# Power.net
KiCad netlist of a schematic drawn in Altium Designer
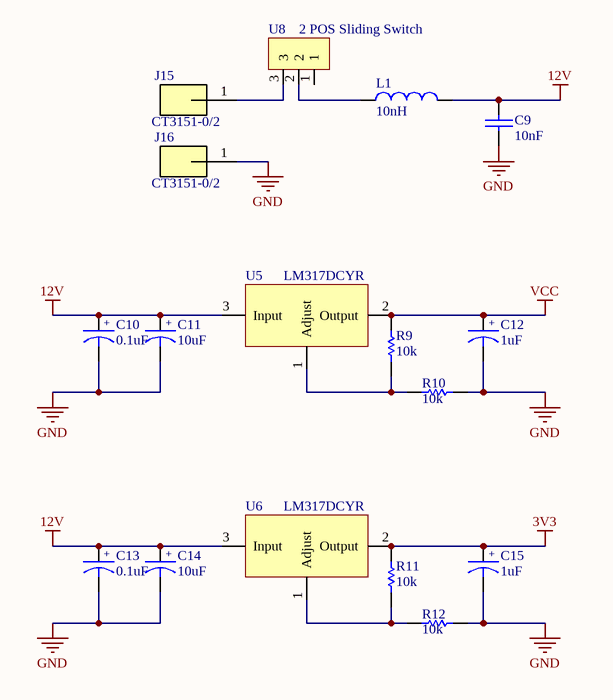
[diagram p0: Power.SchDoc]

(export (version "E")
  (design (tool "Eeschema 10.0.6"))
  (components
    (comp (ref "C9")
      (value "10nF")
      (footprint "0603C")
      (description "Capacitor")
      (libsource (lib "GENERIC_LIB") (part "C"))
    )
    (comp (ref "C10")
      (value "0.1uF")
      (footprint "0603C")
      (description "Cap Poly")
      (libsource (lib "GENERIC_LIB") (part "CPoly"))
    )
    (comp (ref "C11")
      (value "10uF")
      (footprint "0603C")
      (description "Cap Poly")
      (libsource (lib "GENERIC_LIB") (part "CPoly"))
    )
    (comp (ref "C12")
      (value "1uF")
      (footprint "0603C")
      (description "Cap Poly")
      (libsource (lib "GENERIC_LIB") (part "CPoly"))
    )
    (comp (ref "C13")
      (value "0.1uF")
      (footprint "0603C")
      (description "Cap Poly")
      (libsource (lib "GENERIC_LIB") (part "CPoly"))
    )
    (comp (ref "C14")
      (value "10uF")
      (footprint "0603C")
      (description "Cap Poly")
      (libsource (lib "GENERIC_LIB") (part "CPoly"))
    )
    (comp (ref "C15")
      (value "1uF")
      (footprint "0603C")
      (description "Cap Poly")
      (libsource (lib "GENERIC_LIB") (part "CPoly"))
    )
    (comp (ref "J15")
      (value "CT3151-0/2")
      (footprint "CT3151-0/2")
      (description "CONN BANANA JACK SOLDER BLACK")
      (fields
        (field (name "MF") "Cal Test Electronics")
        (field (name "DIGI-KEY_PART_NUMBER") "BKCT3151-0-ND")
      )
      (libsource (lib "CON_LIB") (part "CT3151-0/2"))
    )
    (comp (ref "J16")
      (value "CT3151-0/2")
      (footprint "CT3151-0/2")
      (description "CONN BANANA JACK SOLDER BLACK")
      (fields
        (field (name "MF") "Cal Test Electronics")
        (field (name "DIGI-KEY_PART_NUMBER") "BKCT3151-0-ND")
      )
      (libsource (lib "CON_LIB") (part "CT3151-0/2"))
    )
    (comp (ref "L1")
      (value "10nH")
      (footprint "0603C")
      (description "Inductor")
      (libsource (lib "GENERIC_LIB") (part "L"))
    )
    (comp (ref "R9")
      (value "10k")
      (footprint "0603C")
      (description "Resistor")
      (fields (field (name "TOLERANCE") "5%"))
      (libsource (lib "GENERIC_LIB") (part "R"))
    )
    (comp (ref "R10")
      (value "10k")
      (footprint "0603C")
      (description "Resistor")
      (fields (field (name "TOLERANCE") "5%"))
      (libsource (lib "GENERIC_LIB") (part "R"))
    )
    (comp (ref "R11")
      (value "10k")
      (footprint "0603C")
      (description "Resistor")
      (fields (field (name "TOLERANCE") "5%"))
      (libsource (lib "GENERIC_LIB") (part "R"))
    )
    (comp (ref "R12")
      (value "10k")
      (footprint "0603C")
      (description "Resistor")
      (fields (field (name "TOLERANCE") "5%"))
      (libsource (lib "GENERIC_LIB") (part "R"))
    )
    (comp (ref "U5") (value "LM317DCYR") (footprint "LM317") (libsource (lib "IC_POWER_LIB") (part "LM317")))
    (comp (ref "U6") (value "LM317DCYR") (footprint "LM317") (libsource (lib "IC_POWER_LIB") (part "LM317")))
    (comp (ref "U8")
      (value "2 POS Sliding Switch")
      (footprint "2 POS Sliding switch")
      (libsource (lib "CON_LIB") (part "2 POS Sliding Switch"))
    )
  )
  (nets
    (net (code "1") (name "3V3") (class "Default")
      (node (ref "C15") (pin "1") (pinfunction "1_1") (pintype "passive"))
      (node (ref "R11") (pin "2") (pinfunction "2_2") (pintype "passive"))
      (node (ref "U6") (pin "2") (pinfunction "Output_2") (pintype "passive"))
    )
    (net (code "2") (name "12V") (class "Default")
      (node (ref "C10") (pin "1") (pinfunction "1_1") (pintype "passive"))
      (node (ref "C11") (pin "1") (pinfunction "1_1") (pintype "passive"))
      (node (ref "C13") (pin "1") (pinfunction "1_1") (pintype "passive"))
      (node (ref "C14") (pin "1") (pinfunction "1_1") (pintype "passive"))
      (node (ref "C9") (pin "1") (pinfunction "1_1") (pintype "passive"))
      (node (ref "L1") (pin "2") (pinfunction "2_2") (pintype "passive"))
      (node (ref "U5") (pin "3") (pinfunction "Input_3") (pintype "passive"))
      (node (ref "U6") (pin "3") (pinfunction "Input_3") (pintype "passive"))
    )
    (net (code "3") (name "GND") (class "Default")
      (node (ref "C10") (pin "2") (pinfunction "2_2") (pintype "passive"))
      (node (ref "C11") (pin "2") (pinfunction "2_2") (pintype "passive"))
      (node (ref "C12") (pin "2") (pinfunction "2_2") (pintype "passive"))
      (node (ref "C13") (pin "2") (pinfunction "2_2") (pintype "passive"))
      (node (ref "C14") (pin "2") (pinfunction "2_2") (pintype "passive"))
      (node (ref "C15") (pin "2") (pinfunction "2_2") (pintype "passive"))
      (node (ref "C9") (pin "2") (pinfunction "2_2") (pintype "passive"))
      (node (ref "J16") (pin "1") (pintype "power_in"))
      (node (ref "R10") (pin "2") (pinfunction "2_2") (pintype "passive"))
      (node (ref "R12") (pin "2") (pinfunction "2_2") (pintype "passive"))
    )
    (net (code "4") (name "Net-(J15-Pad1)") (class "Default")
      (node (ref "J15") (pin "1") (pintype "power_in"))
      (node (ref "U8") (pin "3") (pinfunction "3_3") (pintype "passive"))
    )
    (net (code "5") (name "Net-(L1-Pad1)") (class "Default")
      (node (ref "L1") (pin "1") (pinfunction "1_1") (pintype "passive"))
      (node (ref "U8") (pin "2") (pinfunction "2_2") (pintype "passive"))
    )
    (net (code "6") (name "Net-(U5-Adjust)") (class "Default")
      (node (ref "R10") (pin "1") (pinfunction "1_1") (pintype "passive"))
      (node (ref "R9") (pin "1") (pinfunction "1_1") (pintype "passive"))
      (node (ref "U5") (pin "1") (pinfunction "Adjust_1") (pintype "passive"))
    )
    (net (code "7") (name "Net-(U6-Adjust)") (class "Default")
      (node (ref "R11") (pin "1") (pinfunction "1_1") (pintype "passive"))
      (node (ref "R12") (pin "1") (pinfunction "1_1") (pintype "passive"))
      (node (ref "U6") (pin "1") (pinfunction "Adjust_1") (pintype "passive"))
    )
    (net (code "8") (name "VCC") (class "Default")
      (node (ref "C12") (pin "1") (pinfunction "1_1") (pintype "passive"))
      (node (ref "R9") (pin "2") (pinfunction "2_2") (pintype "passive"))
      (node (ref "U5") (pin "2") (pinfunction "Output_2") (pintype "passive"))
    )
    (net (code "9") (name "unconnected-(U8-Pad1)") (class "Default")
      (node (ref "U8") (pin "1") (pinfunction "1_1") (pintype "passive"))
    )
  )
)
